# Peripherals.net
KiCad netlist of a schematic drawn in Altium Designer
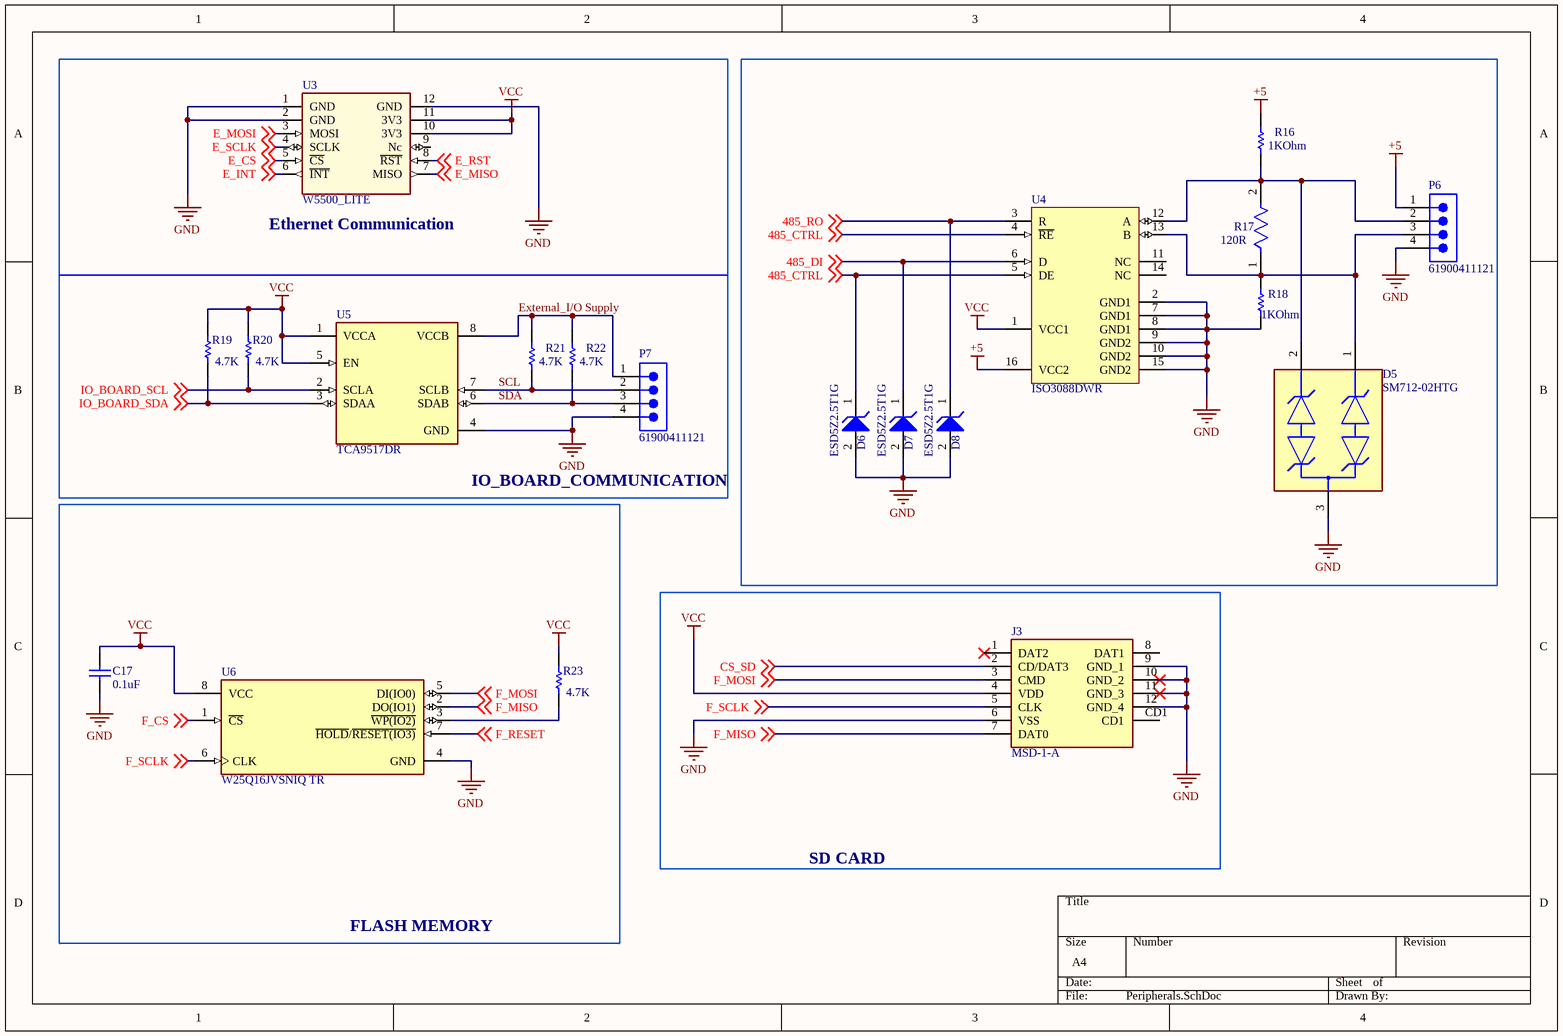
[diagram p0: Peripherals.SchDoc]

(export (version "E")
  (design (tool "Eeschema 10.0.6"))
  (components
    (comp (ref "C17")
      (value "0.1uF")
      (footprint "CAPC1608X92X38ML15T08")
      (fields (field (name "MANUFACTURER") "Vitramon") (field (name "PART NUMBER") "VJ0603Y104KXJAP"))
      (libsource (lib "Altium Content Vault") (part "CAP"))
    )
    (comp (ref "D5")
      (value "SM712-02HTG")
      (footprint "FP-SM712-MFG")
      (description "TVS DIODE 12V 31V SOT23-3")
      (libsource (lib "Altium Content Vault") (part "30adef48d791aa94530531f6d7a3f92"))
    )
    (comp (ref "D6")
      (value "ESD5Z2.5T1G")
      (footprint "ONSC-SOD-523-2-502-01_V")
      (fields (field (name "MANUFACTURER") "On Semiconductor"))
      (libsource (lib "Altium Content Vault") (part "ONSC-K1A2-2"))
    )
    (comp (ref "D7")
      (value "ESD5Z2.5T1G")
      (footprint "ONSC-SOD-523-2-502-01_V")
      (fields (field (name "MANUFACTURER") "On Semiconductor"))
      (libsource (lib "Altium Content Vault") (part "ONSC-K1A2-2"))
    )
    (comp (ref "D8")
      (value "ESD5Z2.5T1G")
      (footprint "ONSC-SOD-523-2-502-01_V")
      (fields (field (name "MANUFACTURER") "On Semiconductor"))
      (libsource (lib "Altium Content Vault") (part "ONSC-K1A2-2"))
    )
    (comp (ref "J3")
      (value "MSD-1-A")
      (footprint "MSD1A")
      (fields (field (name "MOUSER PART NUMBER") "179-MSD-1-A"))
      (libsource (lib "MSD-1-A") (part "MSD-1-A"))
    )
    (comp (ref "P6")
      (value "61900411121")
      (footprint "61900411121")
      (libsource (lib "Altium Content Vault") (part "Header_Male_1R_04P"))
    )
    (comp (ref "P7")
      (value "61900411121")
      (footprint "61900411121")
      (libsource (lib "Altium Content Vault") (part "Header_Male_1R_04P"))
    )
    (comp (ref "R16")
      (value "RC0805FR-071KL")
      (footprint "RESC2013X60X35ML10T20")
      (description "Chip Resistor, 1 KOhm, +/- 1%, 125 mW, -55 to 155 degC, 0805 (2012 Metric), RoHS, Tape and Reel")
      (fields
        (field (name "RESISTANCE") "1KOhm")
        (field (name "TOLERANCE") "1%")
        (field (name "MANUFACTURER") "Yageo")
      )
      (libsource (lib "Altium Content Vault") (part "RES-2"))
    )
    (comp (ref "R17")
      (value "CRCW0805120RFKEA")
      (footprint "FP-CRCW0805-e3-MFG")
      (description "RES Thick Film, 120Ω, 1%, 0.125W, 100ppm/°C, 0805")
      (fields (field (name "RESISTANCE") "120R") (field (name "TOLERANCE") "1%"))
      (libsource (lib "Altium Content Vault") (part "1029c3af85768c4190bb7ad29bc67b5"))
    )
    (comp (ref "R18")
      (value "RC0805FR-071KL")
      (footprint "RESC2013X60X35ML10T20")
      (description "Chip Resistor, 1 KOhm, +/- 1%, 125 mW, -55 to 155 degC, 0805 (2012 Metric), RoHS, Tape and Reel")
      (fields
        (field (name "RESISTANCE") "1KOhm")
        (field (name "TOLERANCE") "1%")
        (field (name "MANUFACTURER") "Yageo")
      )
      (libsource (lib "Altium Content Vault") (part "RES-2"))
    )
    (comp (ref "R19")
      (value "RC0805FR-074K7L")
      (footprint "YAGO-RC0805_M")
      (fields
        (field (name "TOLERANCE") "+/- 1%")
        (field (name "POWER") "0.125 W")
        (field (name "RESISTANCE") "4.7K")
      )
      (libsource (lib "Altium Content Vault") (part "YAGO-RES-2"))
    )
    (comp (ref "R20")
      (value "RC0805FR-074K7L")
      (footprint "YAGO-RC0805_M")
      (fields
        (field (name "TOLERANCE") "+/- 1%")
        (field (name "POWER") "0.125 W")
        (field (name "RESISTANCE") "4.7K")
      )
      (libsource (lib "Altium Content Vault") (part "YAGO-RES-2"))
    )
    (comp (ref "R21")
      (value "RC0805FR-074K7L")
      (footprint "YAGO-RC0805_M")
      (fields
        (field (name "TOLERANCE") "+/- 1%")
        (field (name "POWER") "0.125 W")
        (field (name "RESISTANCE") "4.7K")
      )
      (libsource (lib "Altium Content Vault") (part "YAGO-RES-2"))
    )
    (comp (ref "R22")
      (value "RC0805FR-074K7L")
      (footprint "YAGO-RC0805_M")
      (fields
        (field (name "TOLERANCE") "+/- 1%")
        (field (name "POWER") "0.125 W")
        (field (name "RESISTANCE") "4.7K")
      )
      (libsource (lib "Altium Content Vault") (part "YAGO-RES-2"))
    )
    (comp (ref "R23")
      (value "RC0805FR-074K7L")
      (footprint "YAGO-RC0805_M")
      (fields
        (field (name "TOLERANCE") "+/- 1%")
        (field (name "POWER") "0.125 W")
        (field (name "RESISTANCE") "4.7K")
      )
      (libsource (lib "Altium Content Vault") (part "YAGO-RES-2"))
    )
    (comp (ref "U3") (value "W5500_LITE") (footprint "W5500") (libsource (lib "W5500_LITE") (part "W5500")))
    (comp (ref "U4")
      (value "ISO3088DWR")
      (footprint "DW0016B_N")
      (description "Isolated RS-485 Transceiver, 20 Mbps, 5 V, Half Duplex, -40 to 85 degC, 16-pin SOIC (DW)")
      (fields (field (name "MANUFACTURER") "Texas Instruments"))
      (libsource (lib "Altium Content Vault") (part "TI-ISO3088-SOIC_DW-16"))
    )
    (comp (ref "U5")
      (value "TCA9517DR")
      (footprint "FP-D0008A-MFG")
      (description "IC TRNSLTR BIDIRECTIONAL 8SOIC")
      (libsource (lib "Altium Content Vault") (part "7f4c2d54df977f8cec1530d57da9620"))
    )
    (comp (ref "U6")
      (value "W25Q16JVSNIQ TR")
      (footprint "FP-W25Q16JVSNIQ_TR-IPC_A")
      (description "IC FLASH 16MBIT SPI/QUAD 8SOIC")
      (libsource (lib "Altium Content Vault") (part "bca9062cdd4fd3591131373229c4e34"))
    )
  )
  (nets
    (net (code "1") (name "+5") (class "Default")
      (node (ref "P6") (pin "1") (pinfunction "1_1") (pintype "passive"))
      (node (ref "R16") (pin "2") (pinfunction "2_2") (pintype "passive"))
      (node (ref "U4") (pin "16") (pinfunction "VCC2_16") (pintype "power_in"))
    )
    (net (code "2") (name "/External_I{slash}O Supply") (class "Default")
      (node (ref "P7") (pin "1") (pinfunction "1_1") (pintype "passive"))
      (node (ref "R21") (pin "2") (pinfunction "2_2") (pintype "passive"))
      (node (ref "R22") (pin "2") (pinfunction "2_2") (pintype "passive"))
      (node (ref "U5") (pin "8") (pinfunction "VCCB_8") (pintype "power_in"))
    )
    (net (code "3") (name "/SCL") (class "Default")
      (node (ref "P7") (pin "2") (pinfunction "2_2") (pintype "passive"))
      (node (ref "R21") (pin "1") (pinfunction "1_1") (pintype "passive"))
      (node (ref "U5") (pin "7") (pinfunction "SCLB_7") (pintype "input"))
    )
    (net (code "4") (name "/SDA") (class "Default")
      (node (ref "P7") (pin "3") (pinfunction "3_3") (pintype "passive"))
      (node (ref "R22") (pin "1") (pinfunction "1_1") (pintype "passive"))
      (node (ref "U5") (pin "6") (pinfunction "SDAB_6") (pintype "bidirectional"))
    )
    (net (code "5") (name "485_CTRL") (class "Default")
      (node (ref "D6") (pin "1") (pinfunction "K_1") (pintype "passive"))
      (node (ref "U4") (pin "4") (pinfunction "~{RE}_4") (pintype "input"))
      (node (ref "U4") (pin "5") (pinfunction "DE_5") (pintype "input"))
    )
    (net (code "6") (name "485_DI") (class "Default")
      (node (ref "D7") (pin "1") (pinfunction "K_1") (pintype "passive"))
      (node (ref "U4") (pin "6") (pinfunction "D_6") (pintype "input"))
    )
    (net (code "7") (name "485_RO") (class "Default")
      (node (ref "D8") (pin "1") (pinfunction "K_1") (pintype "passive"))
      (node (ref "U4") (pin "3") (pinfunction "R_3") (pintype "tri_state"))
    )
    (net (code "8") (name "CS_SD") (class "Default")
      (node (ref "J3") (pin "2") (pinfunction "CD/DAT3_2") (pintype "passive"))
    )
    (net (code "9") (name "E_CS") (class "Default")
      (node (ref "U3") (pin "5") (pinfunction "~{CS}_5") (pintype "input"))
    )
    (net (code "10") (name "E_INT") (class "Default")
      (node (ref "U3") (pin "6") (pinfunction "~{INT}_6") (pintype "output"))
    )
    (net (code "11") (name "E_MISO") (class "Default")
      (node (ref "U3") (pin "7") (pinfunction "MISO_7") (pintype "output"))
    )
    (net (code "12") (name "E_MOSI") (class "Default")
      (node (ref "U3") (pin "3") (pinfunction "MOSI_3") (pintype "input"))
    )
    (net (code "13") (name "E_RST") (class "Default")
      (node (ref "U3") (pin "8") (pinfunction "~{RST}_8") (pintype "input"))
    )
    (net (code "14") (name "E_SCLK") (class "Default")
      (node (ref "U3") (pin "4") (pinfunction "SCLK_4") (pintype "bidirectional"))
    )
    (net (code "15") (name "F_CS") (class "Default")
      (node (ref "U6") (pin "1") (pinfunction "~{CS}_1") (pintype "input"))
    )
    (net (code "16") (name "F_MISO") (class "Default")
      (node (ref "J3") (pin "7") (pinfunction "DAT0_7") (pintype "passive"))
      (node (ref "U6") (pin "2") (pinfunction "DO(IO1)_2") (pintype "bidirectional"))
    )
    (net (code "17") (name "F_MOSI") (class "Default")
      (node (ref "J3") (pin "3") (pinfunction "CMD_3") (pintype "passive"))
      (node (ref "U6") (pin "5") (pinfunction "DI(IO0)_5") (pintype "bidirectional"))
    )
    (net (code "18") (name "F_RESET") (class "Default")
      (node (ref "U6") (pin "7") (pinfunction "~{HOLD}/~{RESET(IO3)}_7") (pintype "input"))
    )
    (net (code "19") (name "F_SCLK") (class "Default")
      (node (ref "J3") (pin "5") (pinfunction "CLK_5") (pintype "passive"))
      (node (ref "U6") (pin "6") (pinfunction "CLK_6") (pintype "input"))
    )
    (net (code "20") (name "GND") (class "Default")
      (node (ref "C17") (pin "1") (pinfunction "1_1") (pintype "passive"))
      (node (ref "D5") (pin "3") (pinfunction "3_3") (pintype "passive"))
      (node (ref "D6") (pin "2") (pinfunction "A_2") (pintype "passive"))
      (node (ref "D7") (pin "2") (pinfunction "A_2") (pintype "passive"))
      (node (ref "D8") (pin "2") (pinfunction "A_2") (pintype "passive"))
      (node (ref "J3") (pin "10") (pinfunction "GND_2_10") (pintype "passive"))
      (node (ref "J3") (pin "11") (pinfunction "GND_3_11") (pintype "passive"))
      (node (ref "J3") (pin "12") (pinfunction "GND_4_12") (pintype "passive"))
      (node (ref "J3") (pin "6") (pinfunction "VSS_6") (pintype "passive"))
      (node (ref "J3") (pin "9") (pinfunction "GND_1_9") (pintype "passive"))
      (node (ref "P6") (pin "4") (pinfunction "4_4") (pintype "passive"))
      (node (ref "P7") (pin "4") (pinfunction "4_4") (pintype "passive"))
      (node (ref "R18") (pin "1") (pinfunction "1_1") (pintype "passive"))
      (node (ref "U3") (pin "1") (pinfunction "GND_1") (pintype "power_in"))
      (node (ref "U3") (pin "12") (pinfunction "GND_12") (pintype "power_in"))
      (node (ref "U3") (pin "2") (pinfunction "GND_2") (pintype "power_in"))
      (node (ref "U4") (pin "10") (pinfunction "GND2_10") (pintype "power_in"))
      (node (ref "U4") (pin "15") (pinfunction "GND2_15") (pintype "power_in"))
      (node (ref "U4") (pin "2") (pinfunction "GND1_2") (pintype "power_in"))
      (node (ref "U4") (pin "7") (pinfunction "GND1_7") (pintype "power_in"))
      (node (ref "U4") (pin "8") (pinfunction "GND1_8") (pintype "power_in"))
      (node (ref "U4") (pin "9") (pinfunction "GND2_9") (pintype "power_in"))
      (node (ref "U5") (pin "4") (pinfunction "GND_4") (pintype "power_in"))
      (node (ref "U6") (pin "4") (pinfunction "GND_4") (pintype "power_in"))
    )
    (net (code "21") (name "IO_BOARD_SCL") (class "Default")
      (node (ref "R20") (pin "1") (pinfunction "1_1") (pintype "passive"))
      (node (ref "U5") (pin "2") (pinfunction "SCLA_2") (pintype "input"))
    )
    (net (code "22") (name "IO_BOARD_SDA") (class "Default")
      (node (ref "R19") (pin "1") (pinfunction "1_1") (pintype "passive"))
      (node (ref "U5") (pin "3") (pinfunction "SDAA_3") (pintype "bidirectional"))
    )
    (net (code "23") (name "Net-(U4-A)") (class "Default")
      (node (ref "D5") (pin "2") (pinfunction "2_2") (pintype "passive"))
      (node (ref "P6") (pin "2") (pinfunction "2_2") (pintype "passive"))
      (node (ref "R16") (pin "1") (pinfunction "1_1") (pintype "passive"))
      (node (ref "R17") (pin "2") (pinfunction "2_2") (pintype "passive"))
      (node (ref "U4") (pin "12") (pinfunction "A_12") (pintype "bidirectional"))
    )
    (net (code "24") (name "Net-(U4-B)") (class "Default")
      (node (ref "D5") (pin "1") (pinfunction "1_1") (pintype "passive"))
      (node (ref "P6") (pin "3") (pinfunction "3_3") (pintype "passive"))
      (node (ref "R17") (pin "1") (pinfunction "1_1") (pintype "passive"))
      (node (ref "R18") (pin "2") (pinfunction "2_2") (pintype "passive"))
      (node (ref "U4") (pin "13") (pinfunction "B_13") (pintype "bidirectional"))
    )
    (net (code "25") (name "Net-(U6-~{WP(IO2)})") (class "Default")
      (node (ref "R23") (pin "1") (pinfunction "1_1") (pintype "passive"))
      (node (ref "U6") (pin "3") (pinfunction "~{WP(IO2)}_3") (pintype "bidirectional"))
    )
    (net (code "26") (name "VCC") (class "Default")
      (node (ref "C17") (pin "2") (pinfunction "2_2") (pintype "passive"))
      (node (ref "J3") (pin "4") (pinfunction "VDD_4") (pintype "passive"))
      (node (ref "R19") (pin "2") (pinfunction "2_2") (pintype "passive"))
      (node (ref "R20") (pin "2") (pinfunction "2_2") (pintype "passive"))
      (node (ref "R23") (pin "2") (pinfunction "2_2") (pintype "passive"))
      (node (ref "U3") (pin "10") (pinfunction "3V3_10") (pintype "power_in"))
      (node (ref "U3") (pin "11") (pinfunction "3V3_11") (pintype "power_in"))
      (node (ref "U4") (pin "1") (pinfunction "VCC1_1") (pintype "power_in"))
      (node (ref "U5") (pin "1") (pinfunction "VCCA_1") (pintype "power_in"))
      (node (ref "U5") (pin "5") (pinfunction "EN_5") (pintype "input"))
      (node (ref "U6") (pin "8") (pinfunction "VCC_8") (pintype "power_in"))
    )
    (net (code "27") (name "unconnected-(J3-DAT1-Pad8)") (class "Default")
      (node (ref "J3") (pin "8") (pinfunction "DAT1_8") (pintype "passive"))
    )
    (net (code "28") (name "unconnected-(J3-DAT2-Pad1)") (class "Default")
      (node (ref "J3") (pin "1") (pinfunction "DAT2_1") (pintype "passive+no_connect"))
    )
    (net (code "29") (name "unconnected-(J3-PadCD1)") (class "Default")
      (node (ref "J3") (pin "CD1") (pinfunction "CD1_CD1") (pintype "passive"))
    )
    (net (code "30") (name "unconnected-(U3-Nc-Pad9)") (class "Default")
      (node (ref "U3") (pin "9") (pinfunction "Nc_9") (pintype "bidirectional"))
    )
    (net (code "31") (name "unconnected-(U4-NC-Pad11)") (class "Default")
      (node (ref "U4") (pin "11") (pinfunction "NC_11") (pintype "passive"))
    )
    (net (code "32") (name "unconnected-(U4-NC-Pad14)") (class "Default")
      (node (ref "U4") (pin "14") (pinfunction "NC_14") (pintype "passive"))
    )
  )
)
